# Sheet1.net
KiCad netlist of a schematic drawn in Altium Designer
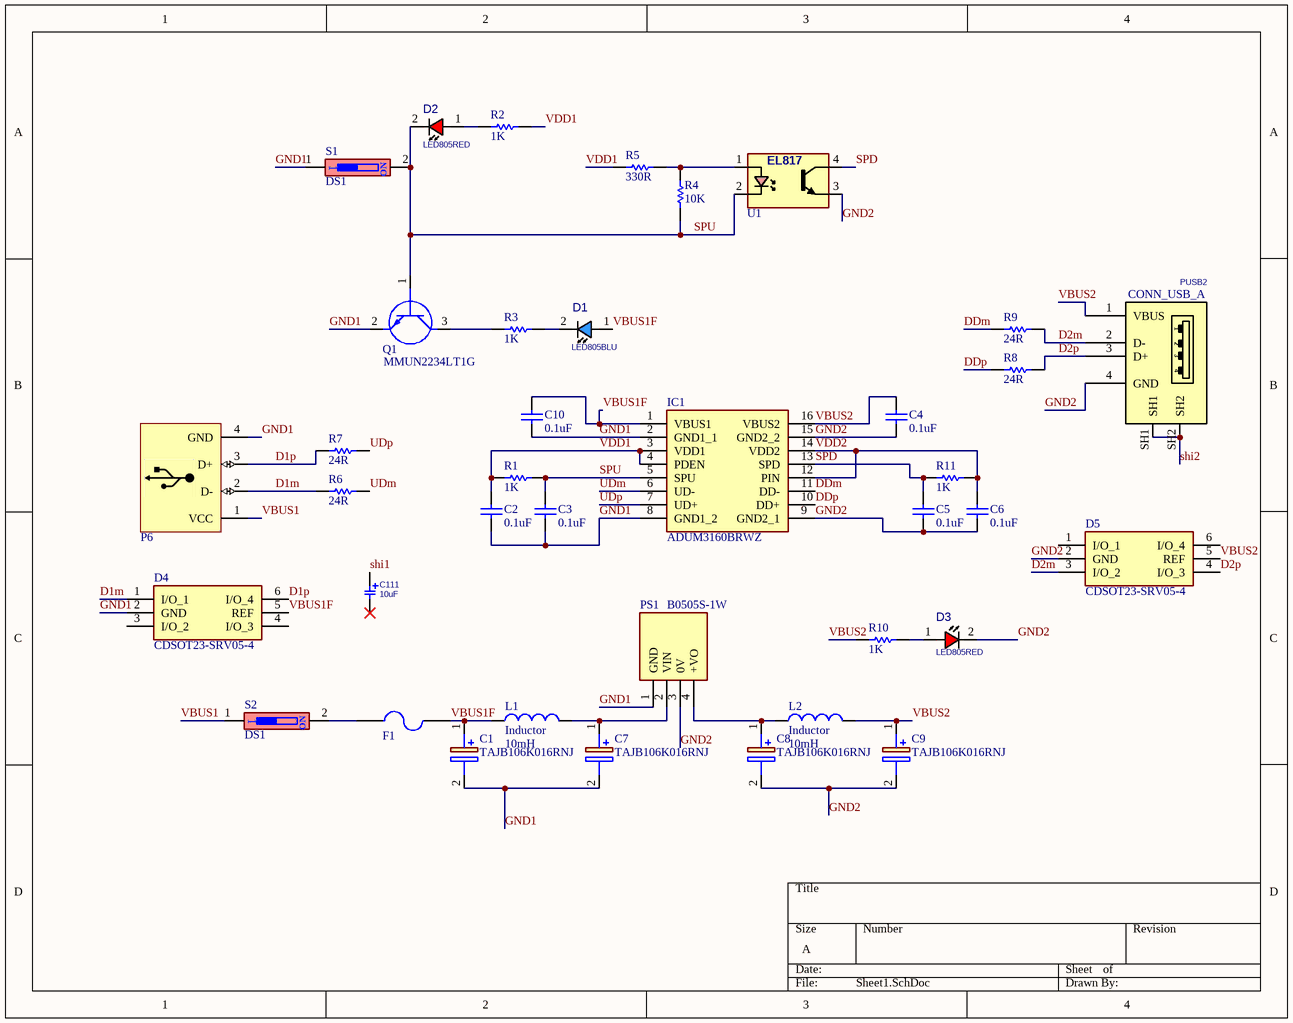
[diagram p0: Sheet1.SchDoc]

(export (version "E")
  (design (tool "Eeschema 10.0.6"))
  (components
    (comp (ref "C1")
      (value "TAJB106K016RNJ")
      (footprint "SamacSys:CAPPM3528X210N")
      (description "Capacitor Polarised")
      (fields (field (name "MOUSER PART NUMBER") "581-TAJB106K016"))
      (libsource (lib "*") (part "TAJB106K016RNJ"))
    )
    (comp (ref "C2")
      (value "0.1uF")
      (footprint "CAPC3413X12N")
      (description "CAP 0805")
      (fields (field (name "DESIGNER") "Abbas Basereh"))
      (libsource (lib "Altium") (part "CAP SMD 0805"))
    )
    (comp (ref "C3")
      (value "0.1uF")
      (footprint "CAPC3413X12N")
      (description "CAP 0805")
      (fields (field (name "DESIGNER") "Abbas Basereh"))
      (libsource (lib "Altium") (part "CAP SMD 0805"))
    )
    (comp (ref "C4")
      (value "0.1uF")
      (footprint "CAPC3413X12N")
      (description "CAP 0805")
      (fields (field (name "DESIGNER") "Abbas Basereh"))
      (libsource (lib "Altium") (part "CAP SMD 0805"))
    )
    (comp (ref "C5")
      (value "0.1uF")
      (footprint "CAPC3413X12N")
      (description "CAP 0805")
      (fields (field (name "DESIGNER") "Abbas Basereh"))
      (libsource (lib "Altium") (part "CAP SMD 0805"))
    )
    (comp (ref "C6")
      (value "0.1uF")
      (footprint "CAPC3413X12N")
      (description "CAP 0805")
      (fields (field (name "DESIGNER") "Abbas Basereh"))
      (libsource (lib "Altium") (part "CAP SMD 0805"))
    )
    (comp (ref "C7")
      (value "TAJB106K016RNJ")
      (footprint "SamacSys:CAPPM3528X210N")
      (description "Capacitor Polarised")
      (fields (field (name "MOUSER PART NUMBER") "581-TAJB106K016"))
      (libsource (lib "*") (part "TAJB106K016RNJ"))
    )
    (comp (ref "C8")
      (value "TAJB106K016RNJ")
      (footprint "SamacSys:CAPPM3528X210N")
      (description "Capacitor Polarised")
      (fields (field (name "MOUSER PART NUMBER") "581-TAJB106K016"))
      (libsource (lib "*") (part "TAJB106K016RNJ"))
    )
    (comp (ref "C9")
      (value "TAJB106K016RNJ")
      (footprint "SamacSys:CAPPM3528X210N")
      (description "Capacitor Polarised")
      (fields (field (name "MOUSER PART NUMBER") "581-TAJB106K016"))
      (libsource (lib "*") (part "TAJB106K016RNJ"))
    )
    (comp (ref "C10")
      (value "0.1uF")
      (footprint "CAPC3413X12N")
      (description "CAP 0805")
      (fields (field (name "DESIGNER") "Abbas Basereh"))
      (libsource (lib "Altium") (part "CAP SMD 0805"))
    )
    (comp (ref "C111")
      (value "10uF")
      (footprint "IND0805")
      (description "CAP, SMD, TAN,")
      (libsource (lib "passive_smd") (part "CAP_SMD_TAN_3216"))
    )
    (comp (ref "D1")
      (value "LED805BLU")
      (footprint "LED0805BLU")
      (description "LED, SMD, 0805, BLUE")
      (fields (field (name "MANF") "MANF") (field (name "MANF_P#") "MANF_PART#"))
      (libsource (lib "led(diode)") (part "LED_SMD_0805_BLU"))
    )
    (comp (ref "D2")
      (value "LED805RED")
      (footprint "LED0805RED")
      (description "LED, SMD, 0805, RED")
      (fields (field (name "MANF") "MANF") (field (name "MANF_P#") "MANF_PART#"))
      (libsource (lib "led(diode)") (part "LED_SMD_0805_RED"))
    )
    (comp (ref "D3")
      (value "LED805RED")
      (footprint "LED0805RED")
      (description "LED, SMD, 0805, RED")
      (fields (field (name "MANF") "MANF") (field (name "MANF_P#") "MANF_PART#"))
      (libsource (lib "led(diode)") (part "LED_SMD_0805_RED"))
    )
    (comp (ref "D4")
      (value "CDSOT23-SRV05-4")
      (footprint "SamacSys:SOT95P280X145-6N")
      (description "TVS Diode (Uni-directional)")
      (fields (field (name "MOUSER PART NUMBER") "652-CDSOT23-SRV05-4"))
      (libsource (lib "*") (part "CDSOT23-SRV05-4"))
    )
    (comp (ref "D5")
      (value "CDSOT23-SRV05-4")
      (footprint "SamacSys:SOT95P280X145-6N")
      (description "TVS Diode (Uni-directional)")
      (fields (field (name "MOUSER PART NUMBER") "652-CDSOT23-SRV05-4"))
      (libsource (lib "*") (part "CDSOT23-SRV05-4"))
    )
    (comp (ref "F1")
      (value "F=1.0 A")
      (footprint "1206 FUSE")
      (description "SMD Fuses 1206")
      (fields (field (name "DESIGNER") "Abbas Basereh"))
      (libsource (lib "Altium") (part "Fuse SMD1206"))
    )
    (comp (ref "IC1")
      (value "ADUM3160BRWZ")
      (footprint "SamacSys:SOIC127P1032X265-16N")
      (description "Integrated Circuit")
      (fields (field (name "MOUSER PART NUMBER") "584-ADUM3160BRWZ"))
      (libsource (lib "*") (part "ADUM3160BRWZ"))
    )
    (comp (ref "L1")
      (value "Inductor")
      (footprint "INDC3216")
      (fields (field (name "ALTIUM_VALUE") "10mH") (field (name "PUBLISHER") "Altium Limited"))
      (libsource (lib "Miscellaneous Devices") (part "Inductor"))
    )
    (comp (ref "L2")
      (value "Inductor")
      (footprint "INDC3216")
      (fields (field (name "ALTIUM_VALUE") "10mH") (field (name "PUBLISHER") "Altium Limited"))
      (libsource (lib "Miscellaneous Devices") (part "Inductor"))
    )
    (comp (ref "P6")
      (value "USB Connector")
      (footprint "USB2.5-2H4F")
      (description "USB Connector-B Type")
      (libsource (lib "Altium") (part "USB B-Type"))
    )
    (comp (ref "PS1")
      (value "B0505S-1W")
      (footprint "SamacSys:B0505S1W")
      (description "Power Supply")
      (libsource (lib "*") (part "B0505S-1W"))
    )
    (comp (ref "PUSB2")
      (value "CONN_USB_A")
      (footprint "USB_A_REC_RA_THD")
      (description "CONN, USB, A, RECEPTACLE, R/A, THD")
      (libsource (lib "conn_usb") (part "CONN_USB_A_REC_RA_THD"))
    )
    (comp (ref "Q1")
      (value "MMUN2234LT1G")
      (footprint "SOT23_3")
      (description "Transistor BJT NPN")
      (fields (field (name "MOUSER PART NUMBER") "863-MMUN2234LT1G"))
      (libsource (lib "*") (part "MMUN2234LT1G"))
    )
    (comp (ref "R1")
      (value "1K")
      (footprint "RESC3413X04N")
      (description "RES 0805")
      (fields (field (name "DESIGNER") "Abbas Basereh"))
      (libsource (lib "Altium") (part "RES 0805 0.125W"))
    )
    (comp (ref "R2")
      (value "1K")
      (footprint "RESC3413X04N")
      (description "RES 0805")
      (fields (field (name "DESIGNER") "Abbas Basereh"))
      (libsource (lib "Altium") (part "RES 0805 0.125W"))
    )
    (comp (ref "R3")
      (value "1K")
      (footprint "RESC3413X04N")
      (description "RES 0805")
      (fields (field (name "DESIGNER") "Abbas Basereh"))
      (libsource (lib "Altium") (part "RES 0805 0.125W"))
    )
    (comp (ref "R4")
      (value "10K")
      (footprint "RESC3413X04N")
      (description "RES 0805")
      (fields (field (name "DESIGNER") "Abbas Basereh"))
      (libsource (lib "Altium") (part "RES 0805 0.125W"))
    )
    (comp (ref "R5")
      (value "330R")
      (footprint "RESC3413X04N")
      (description "RES 0805")
      (fields (field (name "DESIGNER") "Abbas Basereh"))
      (libsource (lib "Altium") (part "RES 0805 0.125W"))
    )
    (comp (ref "R6")
      (value "24R")
      (footprint "RESC3413X04N")
      (description "RES 0805")
      (fields (field (name "DESIGNER") "Abbas Basereh"))
      (libsource (lib "Altium") (part "RES 0805 0.125W"))
    )
    (comp (ref "R7")
      (value "24R")
      (footprint "RESC3413X04N")
      (description "RES 0805")
      (fields (field (name "DESIGNER") "Abbas Basereh"))
      (libsource (lib "Altium") (part "RES 0805 0.125W"))
    )
    (comp (ref "R8")
      (value "24R")
      (footprint "RESC3413X04N")
      (description "RES 0805")
      (fields (field (name "DESIGNER") "Abbas Basereh"))
      (libsource (lib "Altium") (part "RES 0805 0.125W"))
    )
    (comp (ref "R9")
      (value "24R")
      (footprint "RESC3413X04N")
      (description "RES 0805")
      (fields (field (name "DESIGNER") "Abbas Basereh"))
      (libsource (lib "Altium") (part "RES 0805 0.125W"))
    )
    (comp (ref "R10")
      (value "1K")
      (footprint "RESC3413X04N")
      (description "RES 0805")
      (fields (field (name "DESIGNER") "Abbas Basereh"))
      (libsource (lib "Altium") (part "RES 0805 0.125W"))
    )
    (comp (ref "R11")
      (value "1K")
      (footprint "RESC3413X04N")
      (description "RES 0805")
      (fields (field (name "DESIGNER") "Abbas Basereh"))
      (libsource (lib "Altium") (part "RES 0805 0.125W"))
    )
    (comp (ref "S1")
      (value "DS1")
      (footprint "DIP Switch x1")
      (description "1 BIT DIP Switch")
      (libsource (lib "Altium") (part "DIP Switch 1"))
    )
    (comp (ref "S2")
      (value "DS1")
      (footprint "DIP Switch x1")
      (description "1 BIT DIP Switch")
      (libsource (lib "Altium") (part "DIP Switch 1"))
    )
    (comp (ref "U1")
      (value "EL817")
      (footprint "DIP_4")
      (description "OPTOCOUPLER, TRANSISTOR, 4PIN")
      (libsource (lib "optocoupler") (part "OPTC_TR4P_EL817"))
    )
  )
  (nets
    (net (code "1") (name "/D1m") (class "Default")
      (node (ref "D4") (pin "1") (pinfunction "I/O_1_1") (pintype "passive"))
      (node (ref "P6") (pin "2") (pinfunction "D-_2") (pintype "bidirectional"))
      (node (ref "R6") (pin "1") (pinfunction "1_1") (pintype "passive"))
    )
    (net (code "2") (name "/D1p") (class "Default")
      (node (ref "D4") (pin "6") (pinfunction "I/O_4_6") (pintype "passive"))
      (node (ref "P6") (pin "3") (pinfunction "D+_3") (pintype "bidirectional"))
      (node (ref "R7") (pin "1") (pinfunction "1_1") (pintype "passive"))
    )
    (net (code "3") (name "/D2m") (class "Default")
      (node (ref "D5") (pin "3") (pinfunction "I/O_2_3") (pintype "passive"))
      (node (ref "PUSB2") (pin "2") (pinfunction "D-_2") (pintype "passive"))
      (node (ref "R9") (pin "2") (pinfunction "2_2") (pintype "passive"))
    )
    (net (code "4") (name "/D2p") (class "Default")
      (node (ref "D5") (pin "4") (pinfunction "I/O_3_4") (pintype "passive"))
      (node (ref "PUSB2") (pin "3") (pinfunction "D+_3") (pintype "passive"))
      (node (ref "R8") (pin "2") (pinfunction "2_2") (pintype "passive"))
    )
    (net (code "5") (name "/DDm") (class "Default")
      (node (ref "IC1") (pin "11") (pinfunction "DD-_11") (pintype "passive"))
      (node (ref "R9") (pin "1") (pinfunction "1_1") (pintype "passive"))
    )
    (net (code "6") (name "/DDp") (class "Default")
      (node (ref "IC1") (pin "10") (pinfunction "DD+_10") (pintype "passive"))
      (node (ref "R8") (pin "1") (pinfunction "1_1") (pintype "passive"))
    )
    (net (code "7") (name "/GND1") (class "Default")
      (node (ref "C1") (pin "2") (pinfunction "-_2") (pintype "passive"))
      (node (ref "C10") (pin "1") (pinfunction "1_1") (pintype "passive"))
      (node (ref "C2") (pin "1") (pinfunction "1_1") (pintype "passive"))
      (node (ref "C3") (pin "1") (pinfunction "1_1") (pintype "passive"))
      (node (ref "C7") (pin "2") (pinfunction "-_2") (pintype "passive"))
      (node (ref "D4") (pin "2") (pinfunction "GND_2") (pintype "passive"))
      (node (ref "IC1") (pin "2") (pinfunction "GND1_1_2") (pintype "passive"))
      (node (ref "IC1") (pin "8") (pinfunction "GND1_2_8") (pintype "passive"))
      (node (ref "P6") (pin "4") (pinfunction "GND_4") (pintype "power_in"))
      (node (ref "PS1") (pin "1") (pinfunction "GND_1") (pintype "passive"))
      (node (ref "Q1") (pin "2") (pinfunction "E_2") (pintype "passive"))
      (node (ref "S1") (pin "1") (pinfunction "1_1") (pintype "passive"))
    )
    (net (code "8") (name "/GND2") (class "Default")
      (node (ref "C4") (pin "1") (pinfunction "1_1") (pintype "passive"))
      (node (ref "C5") (pin "1") (pinfunction "1_1") (pintype "passive"))
      (node (ref "C6") (pin "1") (pinfunction "1_1") (pintype "passive"))
      (node (ref "C8") (pin "2") (pinfunction "-_2") (pintype "passive"))
      (node (ref "C9") (pin "2") (pinfunction "-_2") (pintype "passive"))
      (node (ref "D3") (pin "2") (pinfunction "CATHODE_2") (pintype "passive"))
      (node (ref "D5") (pin "2") (pinfunction "GND_2") (pintype "passive"))
      (node (ref "IC1") (pin "15") (pinfunction "GND2_2_15") (pintype "passive"))
      (node (ref "IC1") (pin "9") (pinfunction "GND2_1_9") (pintype "passive"))
      (node (ref "PS1") (pin "3") (pinfunction "0V_3") (pintype "passive"))
      (node (ref "PUSB2") (pin "4") (pinfunction "GND_4") (pintype "passive"))
      (node (ref "U1") (pin "3") (pinfunction "E_3") (pintype "passive"))
    )
    (net (code "9") (name "/SPD") (class "Default")
      (node (ref "C5") (pin "2") (pinfunction "2_2") (pintype "passive"))
      (node (ref "IC1") (pin "13") (pinfunction "SPD_13") (pintype "passive"))
      (node (ref "R11") (pin "1") (pinfunction "1_1") (pintype "passive"))
      (node (ref "U1") (pin "4") (pinfunction "C_4") (pintype "passive"))
    )
    (net (code "10") (name "/SPU") (class "Default")
      (node (ref "C3") (pin "2") (pinfunction "2_2") (pintype "passive"))
      (node (ref "D2") (pin "2") (pinfunction "CATHODE_2") (pintype "passive"))
      (node (ref "IC1") (pin "5") (pinfunction "SPU_5") (pintype "passive"))
      (node (ref "Q1") (pin "1") (pinfunction "B_1") (pintype "passive"))
      (node (ref "R1") (pin "2") (pinfunction "2_2") (pintype "passive"))
      (node (ref "R4") (pin "2") (pinfunction "2_2") (pintype "passive"))
      (node (ref "S1") (pin "2") (pinfunction "2_2") (pintype "passive"))
      (node (ref "U1") (pin "2") (pinfunction "K_2") (pintype "passive"))
    )
    (net (code "11") (name "/UDm") (class "Default")
      (node (ref "IC1") (pin "6") (pinfunction "UD-_6") (pintype "passive"))
      (node (ref "R6") (pin "2") (pinfunction "2_2") (pintype "passive"))
    )
    (net (code "12") (name "/UDp") (class "Default")
      (node (ref "IC1") (pin "7") (pinfunction "UD+_7") (pintype "passive"))
      (node (ref "R7") (pin "2") (pinfunction "2_2") (pintype "passive"))
    )
    (net (code "13") (name "/VBUS1") (class "Default")
      (node (ref "P6") (pin "1") (pinfunction "VCC_1") (pintype "power_in"))
      (node (ref "S2") (pin "1") (pinfunction "1_1") (pintype "passive"))
    )
    (net (code "14") (name "/VBUS1F") (class "Default")
      (node (ref "C1") (pin "1") (pinfunction "+_1") (pintype "passive"))
      (node (ref "C10") (pin "2") (pinfunction "2_2") (pintype "passive"))
      (node (ref "D1") (pin "1") (pinfunction "ANODE_1") (pintype "passive"))
      (node (ref "D4") (pin "5") (pinfunction "REF_5") (pintype "passive"))
      (node (ref "F1") (pin "2") (pinfunction "2_2") (pintype "passive"))
      (node (ref "IC1") (pin "1") (pinfunction "VBUS1_1") (pintype "passive"))
      (node (ref "L1") (pin "1") (pinfunction "1_1") (pintype "passive"))
    )
    (net (code "15") (name "/VBUS2") (class "Default")
      (node (ref "C4") (pin "2") (pinfunction "2_2") (pintype "passive"))
      (node (ref "C9") (pin "1") (pinfunction "+_1") (pintype "passive"))
      (node (ref "D5") (pin "5") (pinfunction "REF_5") (pintype "passive"))
      (node (ref "IC1") (pin "16") (pinfunction "VBUS2_16") (pintype "passive"))
      (node (ref "L2") (pin "2") (pinfunction "2_2") (pintype "passive"))
      (node (ref "PUSB2") (pin "1") (pinfunction "VBUS_1") (pintype "passive"))
      (node (ref "R10") (pin "1") (pinfunction "1_1") (pintype "passive"))
    )
    (net (code "16") (name "/VDD1") (class "Default")
      (node (ref "C2") (pin "2") (pinfunction "2_2") (pintype "passive"))
      (node (ref "IC1") (pin "3") (pinfunction "VDD1_3") (pintype "passive"))
      (node (ref "IC1") (pin "4") (pinfunction "PDEN_4") (pintype "passive"))
      (node (ref "R1") (pin "1") (pinfunction "1_1") (pintype "passive"))
      (node (ref "R2") (pin "1") (pinfunction "1_1") (pintype "passive"))
      (node (ref "R5") (pin "1") (pinfunction "1_1") (pintype "passive"))
    )
    (net (code "17") (name "/VDD2") (class "Default")
      (node (ref "C6") (pin "2") (pinfunction "2_2") (pintype "passive"))
      (node (ref "IC1") (pin "12") (pinfunction "PIN_12") (pintype "passive"))
      (node (ref "IC1") (pin "14") (pinfunction "VDD2_14") (pintype "passive"))
      (node (ref "R11") (pin "2") (pinfunction "2_2") (pintype "passive"))
    )
    (net (code "18") (name "/shi1") (class "Default")
      (node (ref "C111") (pin "1") (pinfunction "1_1") (pintype "passive"))
    )
    (net (code "19") (name "/shi2") (class "Default")
      (node (ref "PUSB2") (pin "SH1") (pinfunction "SH1_SH1") (pintype "passive"))
      (node (ref "PUSB2") (pin "SH2") (pinfunction "SH2_SH2") (pintype "passive"))
    )
    (net (code "20") (name "Net-(C7-+)") (class "Default")
      (node (ref "C7") (pin "1") (pinfunction "+_1") (pintype "passive"))
      (node (ref "L1") (pin "2") (pinfunction "2_2") (pintype "passive"))
      (node (ref "PS1") (pin "2") (pinfunction "VIN_2") (pintype "passive"))
    )
    (net (code "21") (name "Net-(C8-+)") (class "Default")
      (node (ref "C8") (pin "1") (pinfunction "+_1") (pintype "passive"))
      (node (ref "L2") (pin "1") (pinfunction "1_1") (pintype "passive"))
      (node (ref "PS1") (pin "4") (pinfunction "+VO_4") (pintype "passive"))
    )
    (net (code "22") (name "Net-(D1-CATHODE)") (class "Default")
      (node (ref "D1") (pin "2") (pinfunction "CATHODE_2") (pintype "passive"))
      (node (ref "R3") (pin "2") (pinfunction "2_2") (pintype "passive"))
    )
    (net (code "23") (name "Net-(D2-ANODE)") (class "Default")
      (node (ref "D2") (pin "1") (pinfunction "ANODE_1") (pintype "passive"))
      (node (ref "R2") (pin "2") (pinfunction "2_2") (pintype "passive"))
    )
    (net (code "24") (name "Net-(D3-ANODE)") (class "Default")
      (node (ref "D3") (pin "1") (pinfunction "ANODE_1") (pintype "passive"))
      (node (ref "R10") (pin "2") (pinfunction "2_2") (pintype "passive"))
    )
    (net (code "25") (name "Net-(F1-Pad1)") (class "Default")
      (node (ref "F1") (pin "1") (pinfunction "1_1") (pintype "passive"))
      (node (ref "S2") (pin "2") (pinfunction "2_2") (pintype "passive"))
    )
    (net (code "26") (name "Net-(Q1-C)") (class "Default")
      (node (ref "Q1") (pin "3") (pinfunction "C_3") (pintype "passive"))
      (node (ref "R3") (pin "1") (pinfunction "1_1") (pintype "passive"))
    )
    (net (code "27") (name "Net-(U1-A)") (class "Default")
      (node (ref "R4") (pin "1") (pinfunction "1_1") (pintype "passive"))
      (node (ref "R5") (pin "2") (pinfunction "2_2") (pintype "passive"))
      (node (ref "U1") (pin "1") (pinfunction "A_1") (pintype "passive"))
    )
    (net (code "28") (name "unconnected-(C111-Pad2)") (class "Default")
      (node (ref "C111") (pin "2") (pinfunction "2_2") (pintype "passive+no_connect"))
    )
    (net (code "29") (name "unconnected-(D4-I{slash}O_2-Pad3)") (class "Default")
      (node (ref "D4") (pin "3") (pinfunction "I/O_2_3") (pintype "passive"))
    )
    (net (code "30") (name "unconnected-(D4-I{slash}O_3-Pad4)") (class "Default")
      (node (ref "D4") (pin "4") (pinfunction "I/O_3_4") (pintype "passive"))
    )
    (net (code "31") (name "unconnected-(D5-I{slash}O_1-Pad1)") (class "Default")
      (node (ref "D5") (pin "1") (pinfunction "I/O_1_1") (pintype "passive"))
    )
    (net (code "32") (name "unconnected-(D5-I{slash}O_4-Pad6)") (class "Default")
      (node (ref "D5") (pin "6") (pinfunction "I/O_4_6") (pintype "passive"))
    )
  )
)
